# serial_led_controller.net
KiCad netlist of a schematic drawn in EAGLE
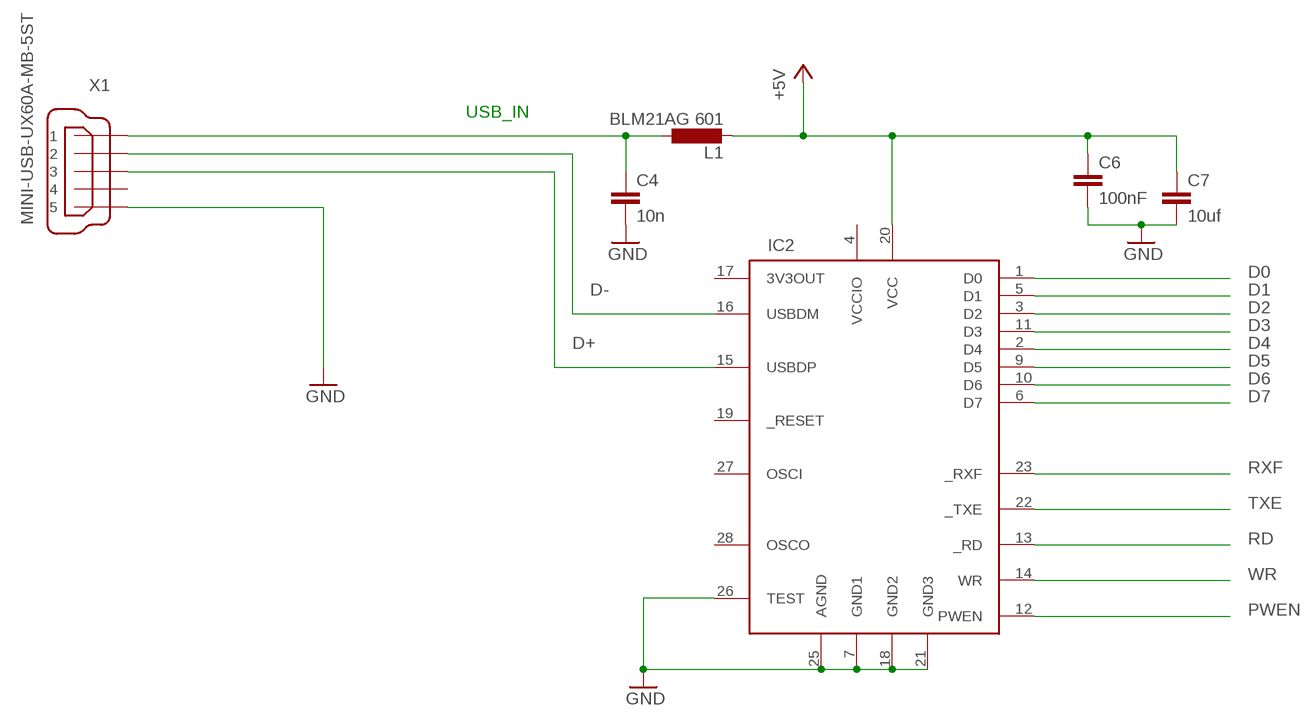
[diagram p0: schematic, sheet 1]
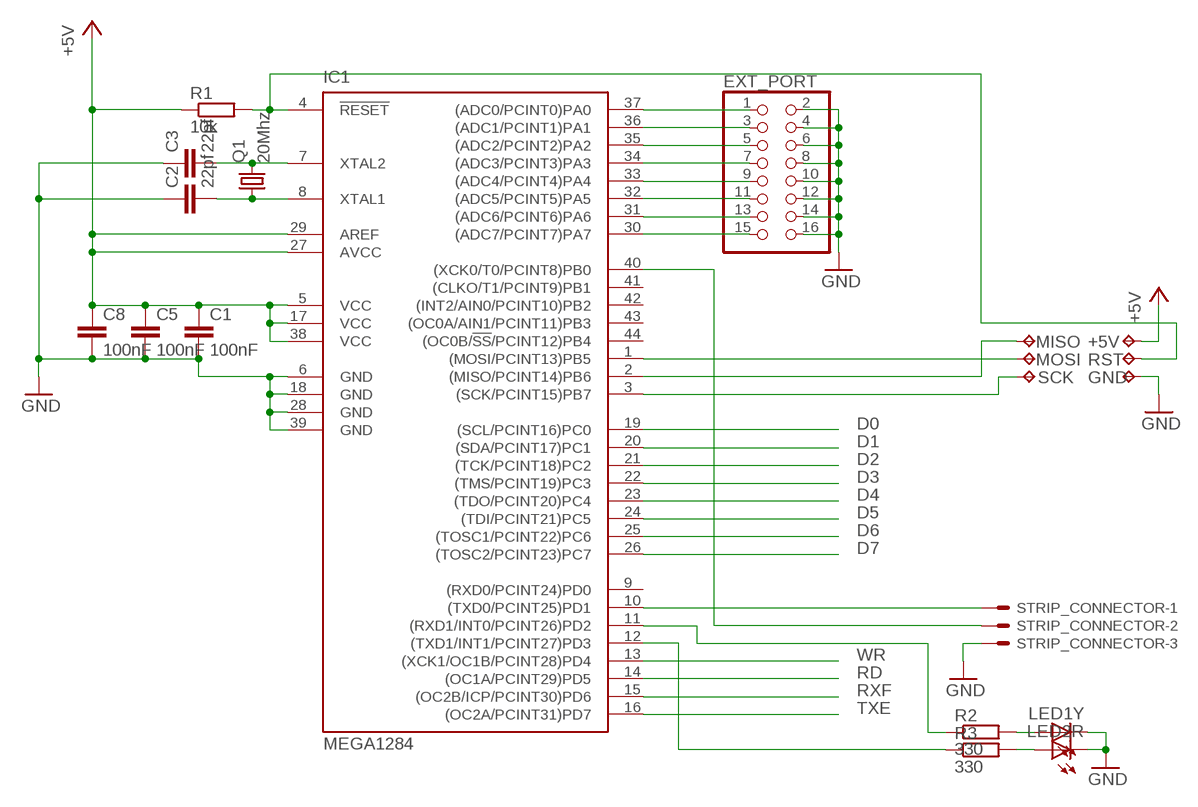
[diagram p1: schematic, sheet 2]

(export (version "E")
  (design (tool "Eeschema 10.0.6"))
  (components
    (comp (ref "C4")
      (value "10n")
      (footprint "eagle-import:C0603K")
      (libsource (lib "eagle-import") (part "C-EUC0603K"))
    )
    (comp (ref "C6")
      (value "100nF")
      (footprint "eagle-import:C0603K")
      (libsource (lib "eagle-import") (part "C-EUC0603K"))
    )
    (comp (ref "C7")
      (value "10uf")
      (footprint "eagle-import:C0603K")
      (libsource (lib "eagle-import") (part "C-EUC0603K"))
    )
    (comp (ref "IC2")
      (value "FT245RL")
      (footprint "eagle-import:SSOP28DB")
      (libsource (lib "eagle-import") (part "FT245RL"))
    )
    (comp (ref "L1")
      (value "BLM21AG 601")
      (footprint "eagle-import:L805")
      (libsource (lib "eagle-import") (part "L-EUL805"))
    )
    (comp (ref "X1")
      (value "MINI-USB-UX60A-MB-5ST")
      (footprint "eagle-import:UX60A-MB-5ST")
      (libsource (lib "eagle-import") (part "MINI-USB-UX60A-MB-5ST"))
    )
    (comp (ref "+5V")
      (value "TPTP19R")
      (footprint "eagle-import:TP19R")
      (libsource (lib "eagle-import") (part "TPTP19R"))
    )
    (comp (ref "C1")
      (value "100nF")
      (footprint "eagle-import:C0603K")
      (libsource (lib "eagle-import") (part "C-EUC0603K"))
    )
    (comp (ref "C2")
      (value "22pf")
      (footprint "eagle-import:C0603K")
      (libsource (lib "eagle-import") (part "C-EUC0603K"))
    )
    (comp (ref "C3")
      (value "22pf")
      (footprint "eagle-import:C0603K")
      (libsource (lib "eagle-import") (part "C-EUC0603K"))
    )
    (comp (ref "C5")
      (value "100nF")
      (footprint "eagle-import:C0603K")
      (libsource (lib "eagle-import") (part "C-EUC0603K"))
    )
    (comp (ref "C8")
      (value "100nF")
      (footprint "eagle-import:C0603K")
      (libsource (lib "eagle-import") (part "C-EUC0603K"))
    )
    (comp (ref "EXT_PORT")
      (value "PINHD-2X8")
      (footprint "eagle-import:2X08")
      (libsource (lib "eagle-import") (part "PINHD-2X8"))
    )
    (comp (ref "GND")
      (value "TPTP19R")
      (footprint "eagle-import:TP19R")
      (libsource (lib "eagle-import") (part "TPTP19R"))
    )
    (comp (ref "IC1")
      (value "MEGA1284")
      (footprint "eagle-import:TQFP44")
      (libsource (lib "eagle-import") (part "MEGA164P/324P/644P-AU"))
    )
    (comp (ref "LED1Y")
      (value "LEDCHIP-LED0603")
      (footprint "eagle-import:CHIP-LED0603")
      (libsource (lib "eagle-import") (part "LEDCHIP-LED0603"))
    )
    (comp (ref "LED2R")
      (value "LEDCHIP-LED0603")
      (footprint "eagle-import:CHIP-LED0603")
      (libsource (lib "eagle-import") (part "LEDCHIP-LED0603"))
    )
    (comp (ref "MISO")
      (value "TPTP19R")
      (footprint "eagle-import:TP19R")
      (libsource (lib "eagle-import") (part "TPTP19R"))
    )
    (comp (ref "MOSI")
      (value "TPTP19R")
      (footprint "eagle-import:TP19R")
      (libsource (lib "eagle-import") (part "TPTP19R"))
    )
    (comp (ref "Q1")
      (value "20Mhz")
      (footprint "eagle-import:SM49")
      (libsource (lib "eagle-import") (part "CRYSTALSM49"))
    )
    (comp (ref "R1")
      (value "10k")
      (footprint "eagle-import:R0603")
      (libsource (lib "eagle-import") (part "R-EU_603"))
    )
    (comp (ref "R2")
      (value "330")
      (footprint "eagle-import:R0603")
      (libsource (lib "eagle-import") (part "R-EU_603"))
    )
    (comp (ref "R3")
      (value "330")
      (footprint "eagle-import:R0603")
      (libsource (lib "eagle-import") (part "R-EU_603"))
    )
    (comp (ref "RST")
      (value "TPTP19R")
      (footprint "eagle-import:TP19R")
      (libsource (lib "eagle-import") (part "TPTP19R"))
    )
    (comp (ref "SCK")
      (value "TPTP19R")
      (footprint "eagle-import:TP19R")
      (libsource (lib "eagle-import") (part "TPTP19R"))
    )
    (comp (ref "STRIP_CONNECTOR")
      (value "22-27-2031-03")
      (footprint "eagle-import:6410-03")
      (libsource (lib "eagle-import") (part "22-?-0327-2031"))
    )
  )
  (nets
    (net (code "1") (name "+5V") (class "Default")
      (node (ref "+5V") (pin "TP") (pinfunction "TP_TP") (pintype "input"))
      (node (ref "C1") (pin "1") (pinfunction "1_1") (pintype "passive"))
      (node (ref "C5") (pin "1") (pinfunction "1_1") (pintype "passive"))
      (node (ref "C6") (pin "1") (pinfunction "1_1") (pintype "passive"))
      (node (ref "C7") (pin "1") (pinfunction "1_1") (pintype "passive"))
      (node (ref "C8") (pin "1") (pinfunction "1_1") (pintype "passive"))
      (node (ref "IC1") (pin "17") (pinfunction "VCC_17") (pintype "power_in"))
      (node (ref "IC1") (pin "27") (pinfunction "AVCC_27") (pintype "power_in"))
      (node (ref "IC1") (pin "29") (pinfunction "AREF_29") (pintype "power_in"))
      (node (ref "IC1") (pin "38") (pinfunction "VCC_38") (pintype "power_in"))
      (node (ref "IC1") (pin "5") (pinfunction "VCC_5") (pintype "power_in"))
      (node (ref "IC2") (pin "20") (pinfunction "VCC_20") (pintype "power_in"))
      (node (ref "L1") (pin "2") (pinfunction "2_2") (pintype "passive"))
      (node (ref "R1") (pin "1") (pinfunction "1_1") (pintype "passive"))
    )
    (net (code "2") (name "D+") (class "Default")
      (node (ref "IC2") (pin "15") (pinfunction "USBDP_15") (pintype "bidirectional"))
      (node (ref "X1") (pin "3") (pinfunction "3_3") (pintype "input"))
    )
    (net (code "3") (name "D-") (class "Default")
      (node (ref "IC2") (pin "16") (pinfunction "USBDM_16") (pintype "bidirectional"))
      (node (ref "X1") (pin "2") (pinfunction "2_2") (pintype "input"))
    )
    (net (code "4") (name "D0") (class "Default")
      (node (ref "IC1") (pin "19") (pinfunction "(SCL/PCINT16)PC0_19") (pintype "bidirectional"))
      (node (ref "IC2") (pin "1") (pinfunction "D0_1") (pintype "output"))
    )
    (net (code "5") (name "D1") (class "Default")
      (node (ref "IC1") (pin "20") (pinfunction "(SDA/PCINT17)PC1_20") (pintype "bidirectional"))
      (node (ref "IC2") (pin "5") (pinfunction "D1_5") (pintype "input"))
    )
    (net (code "6") (name "D2") (class "Default")
      (node (ref "IC1") (pin "21") (pinfunction "(TCK/PCINT18)PC2_21") (pintype "bidirectional"))
      (node (ref "IC2") (pin "3") (pinfunction "D2_3") (pintype "output"))
    )
    (net (code "7") (name "D3") (class "Default")
      (node (ref "IC1") (pin "22") (pinfunction "(TMS/PCINT19)PC3_22") (pintype "bidirectional"))
      (node (ref "IC2") (pin "11") (pinfunction "D3_11") (pintype "input"))
    )
    (net (code "8") (name "D4") (class "Default")
      (node (ref "IC1") (pin "23") (pinfunction "(TDO/PCINT20)PC4_23") (pintype "bidirectional"))
      (node (ref "IC2") (pin "2") (pinfunction "D4_2") (pintype "output"))
    )
    (net (code "9") (name "D5") (class "Default")
      (node (ref "IC1") (pin "24") (pinfunction "(TDI/PCINT21)PC5_24") (pintype "bidirectional"))
      (node (ref "IC2") (pin "9") (pinfunction "D5_9") (pintype "input"))
    )
    (net (code "10") (name "D6") (class "Default")
      (node (ref "IC1") (pin "25") (pinfunction "(TOSC1/PCINT22)PC6_25") (pintype "bidirectional"))
      (node (ref "IC2") (pin "10") (pinfunction "D6_10") (pintype "input"))
    )
    (net (code "11") (name "D7") (class "Default")
      (node (ref "IC1") (pin "26") (pinfunction "(TOSC2/PCINT23)PC7_26") (pintype "bidirectional"))
      (node (ref "IC2") (pin "6") (pinfunction "D7_6") (pintype "input"))
    )
    (net (code "12") (name "GND") (class "Default")
      (node (ref "C1") (pin "2") (pinfunction "2_2") (pintype "passive"))
      (node (ref "C2") (pin "1") (pinfunction "1_1") (pintype "passive"))
      (node (ref "C3") (pin "1") (pinfunction "1_1") (pintype "passive"))
      (node (ref "C4") (pin "2") (pinfunction "2_2") (pintype "passive"))
      (node (ref "C5") (pin "2") (pinfunction "2_2") (pintype "passive"))
      (node (ref "C6") (pin "2") (pinfunction "2_2") (pintype "passive"))
      (node (ref "C7") (pin "2") (pinfunction "2_2") (pintype "passive"))
      (node (ref "C8") (pin "2") (pinfunction "2_2") (pintype "passive"))
      (node (ref "EXT_PORT") (pin "10") (pinfunction "10_10") (pintype "passive"))
      (node (ref "EXT_PORT") (pin "12") (pinfunction "12_12") (pintype "passive"))
      (node (ref "EXT_PORT") (pin "14") (pinfunction "14_14") (pintype "passive"))
      (node (ref "EXT_PORT") (pin "16") (pinfunction "16_16") (pintype "passive"))
      (node (ref "EXT_PORT") (pin "2") (pinfunction "2_2") (pintype "passive"))
      (node (ref "EXT_PORT") (pin "4") (pinfunction "4_4") (pintype "passive"))
      (node (ref "EXT_PORT") (pin "6") (pinfunction "6_6") (pintype "passive"))
      (node (ref "EXT_PORT") (pin "8") (pinfunction "8_8") (pintype "passive"))
      (node (ref "GND") (pin "TP") (pinfunction "TP_TP") (pintype "input"))
      (node (ref "IC1") (pin "18") (pinfunction "GND_18") (pintype "power_in"))
      (node (ref "IC1") (pin "28") (pinfunction "GND_28") (pintype "power_in"))
      (node (ref "IC1") (pin "39") (pinfunction "GND_39") (pintype "power_in"))
      (node (ref "IC1") (pin "6") (pinfunction "GND_6") (pintype "power_in"))
      (node (ref "IC2") (pin "18") (pinfunction "GND2_18") (pintype "power_in"))
      (node (ref "IC2") (pin "21") (pinfunction "GND3_21") (pintype "power_in"))
      (node (ref "IC2") (pin "25") (pinfunction "AGND_25") (pintype "power_in"))
      (node (ref "IC2") (pin "26") (pinfunction "TEST_26") (pintype "input"))
      (node (ref "IC2") (pin "7") (pinfunction "GND1_7") (pintype "power_in"))
      (node (ref "LED1Y") (pin "C") (pinfunction "C_C") (pintype "passive"))
      (node (ref "LED2R") (pin "C") (pinfunction "C_C") (pintype "passive"))
      (node (ref "STRIP_CONNECTOR") (pin "3") (pinfunction "S_3") (pintype "passive"))
      (node (ref "X1") (pin "5") (pinfunction "5_5") (pintype "input"))
    )
    (net (code "13") (name "Net-(C4-Pad1)") (class "Default")
      (node (ref "C4") (pin "1") (pinfunction "1_1") (pintype "passive"))
      (node (ref "L1") (pin "1") (pinfunction "1_1") (pintype "passive"))
      (node (ref "X1") (pin "1") (pinfunction "1_1") (pintype "input"))
    )
    (net (code "14") (name "Net-(IC1-(ADC0{slash}PCINT0)PA0)") (class "Default")
      (node (ref "EXT_PORT") (pin "1") (pinfunction "1_1") (pintype "passive"))
      (node (ref "IC1") (pin "37") (pinfunction "(ADC0/PCINT0)PA0_37") (pintype "bidirectional"))
    )
    (net (code "15") (name "Net-(IC1-(ADC1{slash}PCINT1)PA1)") (class "Default")
      (node (ref "EXT_PORT") (pin "3") (pinfunction "3_3") (pintype "passive"))
      (node (ref "IC1") (pin "36") (pinfunction "(ADC1/PCINT1)PA1_36") (pintype "bidirectional"))
    )
    (net (code "16") (name "Net-(IC1-(ADC2{slash}PCINT2)PA2)") (class "Default")
      (node (ref "EXT_PORT") (pin "5") (pinfunction "5_5") (pintype "passive"))
      (node (ref "IC1") (pin "35") (pinfunction "(ADC2/PCINT2)PA2_35") (pintype "bidirectional"))
    )
    (net (code "17") (name "Net-(IC1-(ADC3{slash}PCINT3)PA3)") (class "Default")
      (node (ref "EXT_PORT") (pin "7") (pinfunction "7_7") (pintype "passive"))
      (node (ref "IC1") (pin "34") (pinfunction "(ADC3/PCINT3)PA3_34") (pintype "bidirectional"))
    )
    (net (code "18") (name "Net-(IC1-(ADC4{slash}PCINT4)PA4)") (class "Default")
      (node (ref "EXT_PORT") (pin "9") (pinfunction "9_9") (pintype "passive"))
      (node (ref "IC1") (pin "33") (pinfunction "(ADC4/PCINT4)PA4_33") (pintype "bidirectional"))
    )
    (net (code "19") (name "Net-(IC1-(ADC5{slash}PCINT5)PA5)") (class "Default")
      (node (ref "EXT_PORT") (pin "11") (pinfunction "11_11") (pintype "passive"))
      (node (ref "IC1") (pin "32") (pinfunction "(ADC5/PCINT5)PA5_32") (pintype "bidirectional"))
    )
    (net (code "20") (name "Net-(IC1-(ADC6{slash}PCINT6)PA6)") (class "Default")
      (node (ref "EXT_PORT") (pin "13") (pinfunction "13_13") (pintype "passive"))
      (node (ref "IC1") (pin "31") (pinfunction "(ADC6/PCINT6)PA6_31") (pintype "bidirectional"))
    )
    (net (code "21") (name "Net-(IC1-(ADC7{slash}PCINT7)PA7)") (class "Default")
      (node (ref "EXT_PORT") (pin "15") (pinfunction "15_15") (pintype "passive"))
      (node (ref "IC1") (pin "30") (pinfunction "(ADC7/PCINT7)PA7_30") (pintype "bidirectional"))
    )
    (net (code "22") (name "Net-(IC1-(MISO{slash}PCINT14)PB6)") (class "Default")
      (node (ref "IC1") (pin "2") (pinfunction "(MISO/PCINT14)PB6_2") (pintype "bidirectional"))
      (node (ref "MISO") (pin "TP") (pinfunction "TP_TP") (pintype "input"))
    )
    (net (code "23") (name "Net-(IC1-(MOSI{slash}PCINT13)PB5)") (class "Default")
      (node (ref "IC1") (pin "1") (pinfunction "(MOSI/PCINT13)PB5_1") (pintype "bidirectional"))
      (node (ref "MOSI") (pin "TP") (pinfunction "TP_TP") (pintype "input"))
    )
    (net (code "24") (name "Net-(IC1-(RXD1{slash}INT0{slash}PCINT26)PD2)") (class "Default")
      (node (ref "IC1") (pin "11") (pinfunction "(RXD1/INT0/PCINT26)PD2_11") (pintype "bidirectional"))
      (node (ref "R2") (pin "1") (pinfunction "1_1") (pintype "passive"))
    )
    (net (code "25") (name "Net-(IC1-(SCK{slash}PCINT15)PB7)") (class "Default")
      (node (ref "IC1") (pin "3") (pinfunction "(SCK/PCINT15)PB7_3") (pintype "bidirectional"))
      (node (ref "SCK") (pin "TP") (pinfunction "TP_TP") (pintype "input"))
    )
    (net (code "26") (name "Net-(IC1-(TXD0{slash}PCINT25)PD1)") (class "Default")
      (node (ref "IC1") (pin "10") (pinfunction "(TXD0/PCINT25)PD1_10") (pintype "bidirectional"))
      (node (ref "STRIP_CONNECTOR") (pin "1") (pinfunction "S_1") (pintype "passive"))
    )
    (net (code "27") (name "Net-(IC1-(TXD1{slash}INT1{slash}PCINT27)PD3)") (class "Default")
      (node (ref "IC1") (pin "12") (pinfunction "(TXD1/INT1/PCINT27)PD3_12") (pintype "bidirectional"))
      (node (ref "R3") (pin "1") (pinfunction "1_1") (pintype "passive"))
    )
    (net (code "28") (name "Net-(IC1-(XCK0{slash}T0{slash}PCINT8)PB0)") (class "Default")
      (node (ref "IC1") (pin "40") (pinfunction "(XCK0/T0/PCINT8)PB0_40") (pintype "bidirectional"))
      (node (ref "STRIP_CONNECTOR") (pin "2") (pinfunction "S_2") (pintype "passive"))
    )
    (net (code "29") (name "Net-(IC1-XTAL1)") (class "Default")
      (node (ref "C2") (pin "2") (pinfunction "2_2") (pintype "passive"))
      (node (ref "IC1") (pin "8") (pinfunction "XTAL1_8") (pintype "input"))
      (node (ref "Q1") (pin "1") (pinfunction "1_1") (pintype "passive"))
    )
    (net (code "30") (name "Net-(IC1-XTAL2)") (class "Default")
      (node (ref "C3") (pin "2") (pinfunction "2_2") (pintype "passive"))
      (node (ref "IC1") (pin "7") (pinfunction "XTAL2_7") (pintype "output"))
      (node (ref "Q1") (pin "2") (pinfunction "2_2") (pintype "passive"))
    )
    (net (code "31") (name "Net-(IC1-~{RESET})") (class "Default")
      (node (ref "IC1") (pin "4") (pinfunction "~{RESET}_4") (pintype "input"))
      (node (ref "R1") (pin "2") (pinfunction "2_2") (pintype "passive"))
      (node (ref "RST") (pin "TP") (pinfunction "TP_TP") (pintype "input"))
    )
    (net (code "32") (name "Net-(LED1Y-PadA)") (class "Default")
      (node (ref "LED1Y") (pin "A") (pinfunction "A_A") (pintype "passive"))
      (node (ref "R2") (pin "2") (pinfunction "2_2") (pintype "passive"))
    )
    (net (code "33") (name "Net-(LED2R-PadA)") (class "Default")
      (node (ref "LED2R") (pin "A") (pinfunction "A_A") (pintype "passive"))
      (node (ref "R3") (pin "2") (pinfunction "2_2") (pintype "passive"))
    )
    (net (code "34") (name "PWEN") (class "Default")
      (node (ref "IC2") (pin "12") (pinfunction "PWEN_12") (pintype "bidirectional"))
    )
    (net (code "35") (name "RD") (class "Default")
      (node (ref "IC1") (pin "14") (pinfunction "(OC1A/PCINT29)PD5_14") (pintype "bidirectional"))
      (node (ref "IC2") (pin "13") (pinfunction "_RD_13") (pintype "bidirectional"))
    )
    (net (code "36") (name "RXF") (class "Default")
      (node (ref "IC1") (pin "15") (pinfunction "(OC2B/ICP/PCINT30)PD6_15") (pintype "bidirectional"))
      (node (ref "IC2") (pin "23") (pinfunction "_RXF_23") (pintype "bidirectional"))
    )
    (net (code "37") (name "TXE") (class "Default")
      (node (ref "IC1") (pin "16") (pinfunction "(OC2A/PCINT31)PD7_16") (pintype "bidirectional"))
      (node (ref "IC2") (pin "22") (pinfunction "_TXE_22") (pintype "bidirectional"))
    )
    (net (code "38") (name "VCCIO") (class "Default")
      (node (ref "IC2") (pin "4") (pinfunction "VCCIO_4") (pintype "power_in"))
    )
    (net (code "39") (name "WR") (class "Default")
      (node (ref "IC1") (pin "13") (pinfunction "(XCK1/OC1B/PCINT28)PD4_13") (pintype "bidirectional"))
      (node (ref "IC2") (pin "14") (pinfunction "WR_14") (pintype "bidirectional"))
    )
    (net (code "40") (name "unconnected-(IC1-(CLKO{slash}T1{slash}PCINT9)PB1-Pad41)") (class "Default")
      (node (ref "IC1") (pin "41") (pinfunction "(CLKO/T1/PCINT9)PB1_41") (pintype "bidirectional"))
    )
    (net (code "41") (name "unconnected-(IC1-(INT2{slash}AIN0{slash}PCINT10)PB2-Pad42)") (class "Default")
      (node (ref "IC1") (pin "42") (pinfunction "(INT2/AIN0/PCINT10)PB2_42") (pintype "bidirectional"))
    )
    (net (code "42") (name "unconnected-(IC1-(OC0A{slash}AIN1{slash}PCINT11)PB3-Pad43)") (class "Default")
      (node (ref "IC1") (pin "43") (pinfunction "(OC0A/AIN1/PCINT11)PB3_43") (pintype "bidirectional"))
    )
    (net (code "43") (name "unconnected-(IC1-(OC0B{slash}~{SS}{slash}PCINT12)PB4-Pad44)") (class "Default")
      (node (ref "IC1") (pin "44") (pinfunction "(OC0B/~{SS}/PCINT12)PB4_44") (pintype "bidirectional"))
    )
    (net (code "44") (name "unconnected-(IC1-(RXD0{slash}PCINT24)PD0-Pad9)") (class "Default")
      (node (ref "IC1") (pin "9") (pinfunction "(RXD0/PCINT24)PD0_9") (pintype "bidirectional"))
    )
    (net (code "45") (name "unconnected-(IC2-3V3OUT-Pad17)") (class "Default")
      (node (ref "IC2") (pin "17") (pinfunction "3V3OUT_17") (pintype "output"))
    )
    (net (code "46") (name "unconnected-(IC2-OSCI-Pad27)") (class "Default")
      (node (ref "IC2") (pin "27") (pinfunction "OSCI_27") (pintype "input"))
    )
    (net (code "47") (name "unconnected-(IC2-OSCO-Pad28)") (class "Default")
      (node (ref "IC2") (pin "28") (pinfunction "OSCO_28") (pintype "output"))
    )
    (net (code "48") (name "unconnected-(IC2-_RESET-Pad19)") (class "Default")
      (node (ref "IC2") (pin "19") (pinfunction "_RESET_19") (pintype "input"))
    )
    (net (code "49") (name "unconnected-(X1-Pad4)") (class "Default")
      (node (ref "X1") (pin "4") (pinfunction "4_4") (pintype "input"))
    )
  )
)
